# Sheet1.net
KiCad netlist of a schematic drawn in Altium Designer
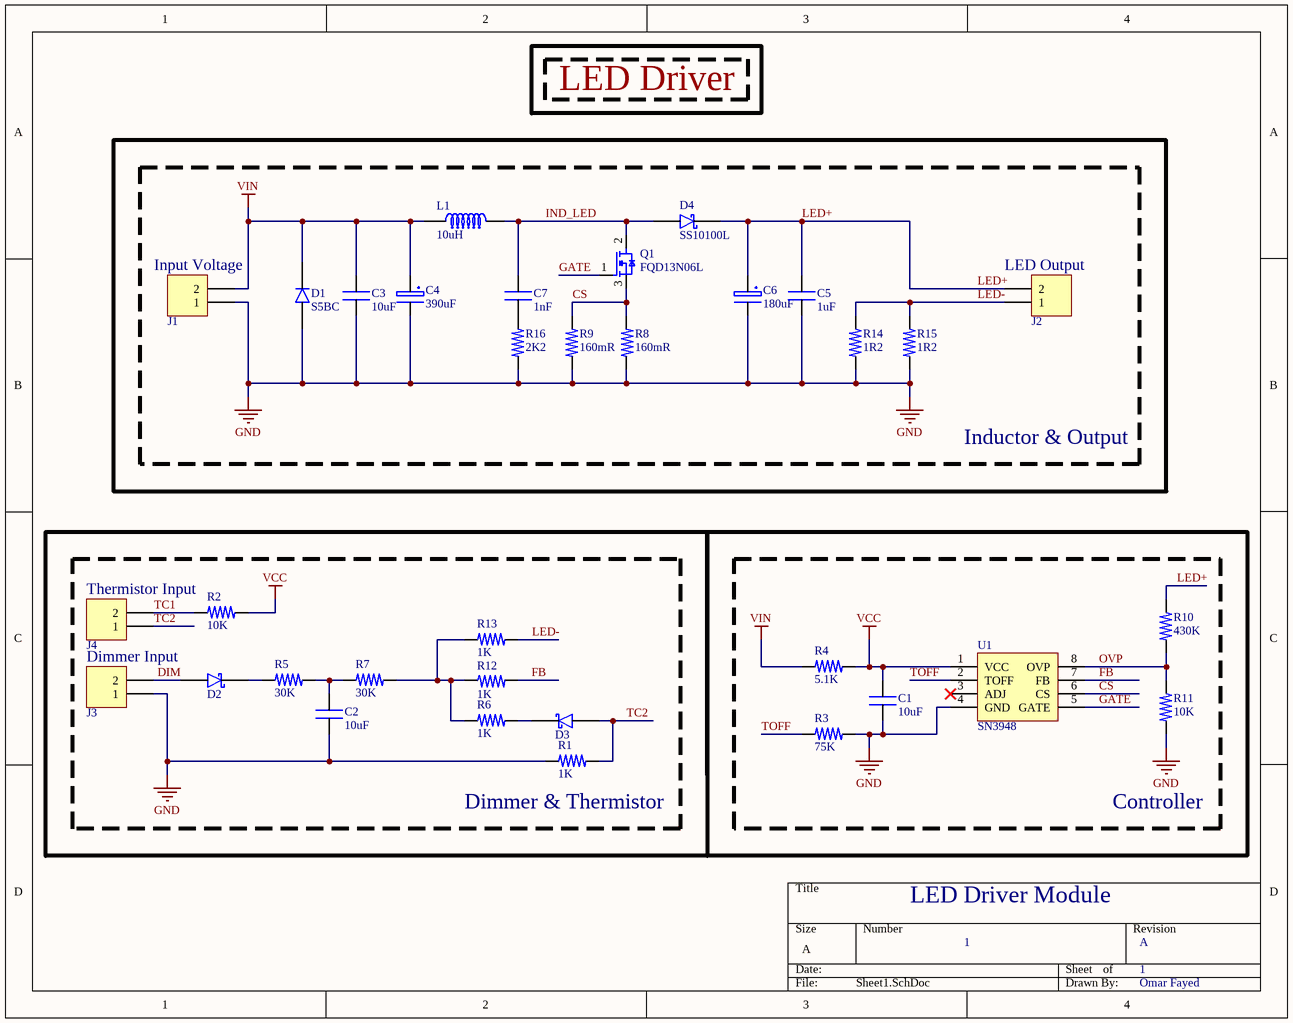
[diagram p0: Sheet1.SchDoc]

(export (version "E")
  (design (tool "Eeschema 10.0.6"))
  (components
    (comp (ref "C1")
      (value "10uF")
      (footprint "CAP Ceramic SMD 0805")
      (description "50V 10uF X5R ±10% 0805 Multilayer Ceramic Capacitors MLCC - SMD/SMT ROHS")
      (fields
        (field (name "MANUFACTURER") "Murata Electronics")
        (field (name "MANUFACTURER PART NUMBER") "GRM21BR61H106KE43L")
      )
      (libsource (lib "Schlib") (part "CAP SMD 0805 10uF 50V"))
    )
    (comp (ref "C2")
      (value "10uF")
      (footprint "CAP Ceramic SMD 0805")
      (description "50V 10uF X5R ±10% 0805 Multilayer Ceramic Capacitors MLCC - SMD/SMT ROHS")
      (fields
        (field (name "MANUFACTURER") "Murata Electronics")
        (field (name "MANUFACTURER PART NUMBER") "GRM21BR61H106KE43L")
      )
      (libsource (lib "Schlib") (part "CAP SMD 0805 10uF 50V"))
    )
    (comp (ref "C3")
      (value "10uF")
      (footprint "CAP Ceramic SMD 0805")
      (description "50V 10uF X5R ±10% 0805 Multilayer Ceramic Capacitors MLCC - SMD/SMT ROHS")
      (fields
        (field (name "MANUFACTURER") "Murata Electronics")
        (field (name "MANUFACTURER PART NUMBER") "GRM21BR61H106KE43L")
      )
      (libsource (lib "Schlib") (part "CAP SMD 0805 10uF 50V"))
    )
    (comp (ref "C4")
      (value "390uF")
      (footprint "CAP Electrolytic TH D8C3.5H11.5 (H)")
      (fields (field (name "MANUFACTURER") "Ymin") (field (name "MANUFACTURER PART NUMBER") "LKME2001J391MF"))
      (libsource (lib "Schlib") (part "CAP POL 390uF 63V"))
    )
    (comp (ref "C5")
      (value "1uF")
      (footprint "CAP Ceramic SMD 1206")
      (description "100V 1uF X7R ±10% 1206 Multilayer Ceramic Capacitors MLCC - SMD/SMT ROHS")
      (fields
        (field (name "MANUFACTURER") "YAGEO")
        (field (name "MANUFACTURER PART NUMBER") "CC1206KKX7R0BB105")
      )
      (libsource (lib "Schlib") (part "CAP SMD 1206 1uF 100V"))
    )
    (comp (ref "C6")
      (value "180uF")
      (footprint "CAP Electrolytic TH D8C3.5H11.5 (H)")
      (fields
        (field (name "MANUFACTURER") "SamYoung Electronics")
        (field (name "MANUFACTURER PART NUMBER") "NXA50V180M8*20 LO")
      )
      (libsource (lib "Schlib") (part "CAP POL 180uF 50V"))
    )
    (comp (ref "C7")
      (value "1nF")
      (footprint "CAP Ceramic SMD 0805")
      (description "100V 1nF NP0 ±5% 0805 Multilayer Ceramic Capacitors MLCC - SMD/SMT ROHS")
      (fields
        (field (name "MANUFACTURER") "YAGEO")
        (field (name "MANUFACTURER PART NUMBER") "CC0805JRNPO0BN102")
      )
      (libsource (lib "Schlib") (part "CAP SMD 0805 1nF"))
    )
    (comp (ref "D1")
      (value "S5BC")
      (footprint "SMC")
      (description "5A 100V 1.15V@5A SMC(DO-214AB) Diodes - General Purpose ROHS")
      (fields
        (field (name "MANUFACTURER") "Diodes Incorporated")
        (field (name "MANUFACTURER PART NUMBER") "S5BC-13-F")
      )
      (libsource (lib "Schlib") (part "S5BC"))
    )
    (comp (ref "D2")
      (value "DIODE SMD BAT54WB")
      (footprint "SOD-323")
      (description "30V 100mA 240mV@100mA SOD-323W Schottky Diodes ROHS")
      (fields
        (field (name "MANUFACTURER") "Shandong Jingdao Microelectronics")
        (field (name "MANUFACTURER PART NUMBER") "BAT54WB")
      )
      (libsource (lib "Schlib") (part "DIODE SMD BAT54WB"))
    )
    (comp (ref "D3")
      (value "DIODE SMD BAT54WB")
      (footprint "SOD-323")
      (description "30V 100mA 240mV@100mA SOD-323W Schottky Diodes ROHS")
      (fields
        (field (name "MANUFACTURER") "Shandong Jingdao Microelectronics")
        (field (name "MANUFACTURER PART NUMBER") "BAT54WB")
      )
      (libsource (lib "Schlib") (part "DIODE SMD BAT54WB"))
    )
    (comp (ref "D4")
      (value "SS10100L")
      (footprint "DO-214AA")
      (description "100V 10A 700mV SMB Schottky Diodes ROHS")
      (fields (field (name "MANUFACTURER") "GOODWORK"))
      (libsource (lib "Schlib") (part "SS10100L"))
    )
    (comp (ref "J1")
      (value "ScrewTerminal 2P mm")
      (footprint "Connector screw terminal Block TH 1x2 9.5 WJ46-B")
      (fields
        (field (name "MANUFACTURER") "MAX")
        (field (name "MANUFACTURER PART NUMBER") "MX126-5.0-02P-GN01-Cu-S-A")
      )
      (libsource (lib "Schlib") (part "ScrewTerminal 2P mm"))
    )
    (comp (ref "J2")
      (value "ScrewTerminal 2P mm")
      (footprint "Connector screw terminal Block TH 1x2 9.5 WJ46-B")
      (fields
        (field (name "MANUFACTURER") "MAX")
        (field (name "MANUFACTURER PART NUMBER") "MX126-5.0-02P-GN01-Cu-S-A")
      )
      (libsource (lib "") (part "ScrewTerminal 2P mm_1"))
    )
    (comp (ref "J3")
      (value "ScrewTerminal 2P mm")
      (footprint "Connector screw terminal Block TH 1x2 9.5 WJ46-B")
      (fields
        (field (name "MANUFACTURER") "MAX")
        (field (name "MANUFACTURER PART NUMBER") "MX126-5.0-02P-GN01-Cu-S-A")
      )
      (libsource (lib "Schlib") (part "ScrewTerminal 2P mm"))
    )
    (comp (ref "J4")
      (value "ScrewTerminal 2P mm")
      (footprint "Connector screw terminal Block TH 1x2 9.5 WJ46-B")
      (fields
        (field (name "MANUFACTURER") "MAX")
        (field (name "MANUFACTURER PART NUMBER") "MX126-5.0-02P-GN01-Cu-S-A")
      )
      (libsource (lib "Schlib") (part "ScrewTerminal 2P mm"))
    )
    (comp (ref "L1")
      (value "10uH")
      (footprint "IND SMD 1365")
      (description "10A 10uH ±20% 13A 19.2mΩ SMD,12.6x13.5mm Inductors (SMD) ROHS")
      (fields
        (field (name "MANUFACTURER") "KOHERelec")
        (field (name "MANUFACTURER PART NUMBER") "MDA1365-100M")
      )
      (libsource (lib "Schlib") (part "IND SMD 1365 10uH"))
    )
    (comp (ref "Q1")
      (value "FQD13N06L")
      (footprint "TO252_2")
      (description "60V 11A 115mΩ@10V,5.5A 2.5V@250uA 1 N-Channel TO-252AA MOSFETs ROHS")
      (fields (field (name "MANUFACTURER") "onsemi") (field (name "MANUFACTURER PART NUMBER") "FQD13N06LTM"))
      (libsource (lib "Schlib") (part "FQD13N06L"))
    )
    (comp (ref "R1")
      (value "1K")
      (footprint "RES SMD 0805")
      (fields
        (field (name "MANUFACTURER") "YAGEO")
        (field (name "MANUFACTURER PART NUMBER") "RC0805FR-071KL")
      )
      (libsource (lib "Schlib") (part "RES SMD 0805 1K"))
    )
    (comp (ref "R2")
      (value "10K")
      (footprint "RES SMD 0805")
      (description "125mW Thick Film Resistors 150V ±100ppm/℃ ±1% 10kΩ 0805 Chip Resistor - Surface Mount ROHS")
      (fields
        (field (name "MANUFACTURER") "YAGEO")
        (field (name "MANUFACTURER PART NUMBER") "RC0805FR-0710KL")
      )
      (libsource (lib "Schlib") (part "RES SMD 0805 10K"))
    )
    (comp (ref "R3")
      (value "75K")
      (footprint "RES SMD 0805")
      (description "125mW Thick Film Resistors 150V ±100ppm/℃ ±1% 75kΩ 0805 Chip Resistor - Surface Mount ROHS")
      (fields
        (field (name "MANUFACTURER") "YAGEO")
        (field (name "MANUFACTURER PART NUMBER") "RC0805FR-0775KL")
      )
      (libsource (lib "Schlib") (part "RES SMD 0805 75K"))
    )
    (comp (ref "R4")
      (value "5.1K")
      (footprint "RES SMD 0805")
      (description "400mW Thick Film Resistors 150V ±200ppm/℃ ±5% 5.1kΩ 0805 Chip Resistor - Surface Mount ROHS")
      (fields
        (field (name "MANUFACTURER") "ROHM Semicon")
        (field (name "MANUFACTURER PART NUMBER") "ESR10EZPJ512")
      )
      (libsource (lib "Schlib") (part "RES SMD 0805 5.1K"))
    )
    (comp (ref "R5")
      (value "30K")
      (footprint "RES SMD 0805")
      (fields (field (name "MANUFACTURER") "FOJAN") (field (name "MANUFACTURER PART NUMBER") "FRC0805J303TS"))
      (libsource (lib "Schlib") (part "RES SMD 0805 30K"))
    )
    (comp (ref "R6")
      (value "1K")
      (footprint "RES SMD 0805")
      (fields
        (field (name "MANUFACTURER") "YAGEO")
        (field (name "MANUFACTURER PART NUMBER") "RC0805FR-071KL")
      )
      (libsource (lib "Schlib") (part "RES SMD 0805 1K"))
    )
    (comp (ref "R7")
      (value "30K")
      (footprint "RES SMD 0805")
      (fields (field (name "MANUFACTURER") "FOJAN") (field (name "MANUFACTURER PART NUMBER") "FRC0805J303TS"))
      (libsource (lib "Schlib") (part "RES SMD 0805 30K"))
    )
    (comp (ref "R8")
      (value "160mR")
      (footprint "RES SMD 1206")
      (description "500mW Thick Film Resistors 200V ±1% 160mΩ 1206 Chip Resistor - Surface Mount ROHS")
      (fields
        (field (name "MANUFACTURER") "UNI-ROYAL(Uniroyal Elec)")
        (field (name "MANUFACTURER PART NUMBER") "HP06W2F160LT5E")
      )
      (libsource (lib "Schlib") (part "RES SMD 1206 160mR"))
    )
    (comp (ref "R9")
      (value "160mR")
      (footprint "RES SMD 1206")
      (description "500mW Thick Film Resistors 200V ±1% 160mΩ 1206 Chip Resistor - Surface Mount ROHS")
      (fields
        (field (name "MANUFACTURER") "UNI-ROYAL(Uniroyal Elec)")
        (field (name "MANUFACTURER PART NUMBER") "HP06W2F160LT5E")
      )
      (libsource (lib "Schlib") (part "RES SMD 1206 160mR"))
    )
    (comp (ref "R10")
      (value "430K")
      (footprint "RES SMD 0805")
      (description "125mW Thick Film Resistors 150V ±100ppm/℃ ±5% 430kΩ 0805 Chip Resistor - Surface Mount ROHS")
      (fields
        (field (name "MANUFACTURER") "YAGEO")
        (field (name "MANUFACTURER PART NUMBER") "RC0805JR-07430KL")
      )
      (libsource (lib "Schlib") (part "RES SMD 0805 430K"))
    )
    (comp (ref "R11")
      (value "10K")
      (footprint "RES SMD 0805")
      (description "125mW Thick Film Resistors 150V ±100ppm/℃ ±1% 10kΩ 0805 Chip Resistor - Surface Mount ROHS")
      (fields
        (field (name "MANUFACTURER") "YAGEO")
        (field (name "MANUFACTURER PART NUMBER") "RC0805FR-0710KL")
      )
      (libsource (lib "Schlib") (part "RES SMD 0805 10K"))
    )
    (comp (ref "R12")
      (value "1K")
      (footprint "RES SMD 0805")
      (fields
        (field (name "MANUFACTURER") "YAGEO")
        (field (name "MANUFACTURER PART NUMBER") "RC0805FR-071KL")
      )
      (libsource (lib "Schlib") (part "RES SMD 0805 1K"))
    )
    (comp (ref "R13")
      (value "1K")
      (footprint "RES SMD 0805")
      (fields
        (field (name "MANUFACTURER") "YAGEO")
        (field (name "MANUFACTURER PART NUMBER") "RC0805FR-071KL")
      )
      (libsource (lib "Schlib") (part "RES SMD 0805 1K"))
    )
    (comp (ref "R14")
      (value "1R2")
      (footprint "RES SMD 1206")
      (description "500mW Thick Film Resistors ±200ppm/℃ ±1% 1.2Ω 1206 Chip Resistor - Surface Mount ROHS")
      (fields
        (field (name "MANUFACTURER") "YAGEO")
        (field (name "MANUFACTURER PART NUMBER") "RC1206FR-7W1R2L")
      )
      (libsource (lib "Schlib") (part "RES SMD 1206 1R20"))
    )
    (comp (ref "R15")
      (value "1R2")
      (footprint "RES SMD 1206")
      (description "500mW Thick Film Resistors ±200ppm/℃ ±1% 1.2Ω 1206 Chip Resistor - Surface Mount ROHS")
      (fields
        (field (name "MANUFACTURER") "YAGEO")
        (field (name "MANUFACTURER PART NUMBER") "RC1206FR-7W1R2L")
      )
      (libsource (lib "Schlib") (part "RES SMD 1206 1R20"))
    )
    (comp (ref "R16")
      (value "2K2")
      (footprint "RES SMD 0805")
      (fields
        (field (name "MANUFACTURER") "YAGEO")
        (field (name "MANUFACTURER PART NUMBER") "RC0805FR-072K2L")
      )
      (libsource (lib "Schlib") (part "RES SMD 0805 2K2"))
    )
    (comp (ref "U1")
      (value "SN3948")
      (footprint "SN3948_SOP8")
      (description "SOP-8 DC-DC Converters ROHS")
      (fields (field (name "MANUFACTURER") "ISSI"))
      (libsource (lib "Schlib") (part "SN3948"))
    )
  )
  (nets
    (net (code "1") (name "/CS") (class "Default")
      (node (ref "Q1") (pin "3") (pinfunction "S_3") (pintype "passive"))
      (node (ref "R8") (pin "1") (pinfunction "1_1") (pintype "passive"))
      (node (ref "R9") (pin "2") (pinfunction "2_2") (pintype "passive"))
      (node (ref "U1") (pin "6") (pinfunction "CS_6") (pintype "passive"))
    )
    (net (code "2") (name "/DIM") (class "Default")
      (node (ref "D2") (pin "1") (pinfunction "1_1") (pintype "passive"))
      (node (ref "J3") (pin "2") (pinfunction "2_2") (pintype "passive"))
    )
    (net (code "3") (name "/FB") (class "Default")
      (node (ref "R12") (pin "1") (pinfunction "1_1") (pintype "passive"))
      (node (ref "U1") (pin "7") (pinfunction "FB_7") (pintype "passive"))
    )
    (net (code "4") (name "/GATE") (class "Default")
      (node (ref "Q1") (pin "1") (pinfunction "G_1") (pintype "passive"))
      (node (ref "U1") (pin "5") (pinfunction "GATE_5") (pintype "passive"))
    )
    (net (code "5") (name "/IND_LED") (class "Default")
      (node (ref "C7") (pin "2") (pinfunction "2_2") (pintype "passive"))
      (node (ref "D4") (pin "1") (pinfunction "1_1") (pintype "passive"))
      (node (ref "L1") (pin "2") (pinfunction "2_2") (pintype "passive"))
      (node (ref "Q1") (pin "2") (pinfunction "D_2") (pintype "passive"))
    )
    (net (code "6") (name "/LED+") (class "Default")
      (node (ref "C5") (pin "2") (pinfunction "2_2") (pintype "passive"))
      (node (ref "C6") (pin "1") (pinfunction "1_1") (pintype "passive"))
      (node (ref "D4") (pin "2") (pinfunction "2_2") (pintype "passive"))
      (node (ref "J2") (pin "2") (pinfunction "2_2") (pintype "passive"))
      (node (ref "R10") (pin "2") (pinfunction "2_2") (pintype "passive"))
    )
    (net (code "7") (name "/LED-") (class "Default")
      (node (ref "J2") (pin "1") (pinfunction "1_1") (pintype "passive"))
      (node (ref "R13") (pin "2") (pinfunction "2_2") (pintype "passive"))
      (node (ref "R14") (pin "2") (pinfunction "2_2") (pintype "passive"))
      (node (ref "R15") (pin "2") (pinfunction "2_2") (pintype "passive"))
    )
    (net (code "8") (name "/OVP") (class "Default")
      (node (ref "R10") (pin "1") (pinfunction "1_1") (pintype "passive"))
      (node (ref "R11") (pin "2") (pinfunction "2_2") (pintype "passive"))
      (node (ref "U1") (pin "8") (pinfunction "OVP_8") (pintype "passive"))
    )
    (net (code "9") (name "/TC1") (class "Default")
      (node (ref "J4") (pin "2") (pinfunction "2_2") (pintype "passive"))
      (node (ref "R2") (pin "1") (pinfunction "1_1") (pintype "passive"))
    )
    (net (code "10") (name "/TC2") (class "Default")
      (node (ref "D3") (pin "1") (pinfunction "1_1") (pintype "passive"))
      (node (ref "J4") (pin "1") (pinfunction "1_1") (pintype "passive"))
      (node (ref "R1") (pin "2") (pinfunction "2_2") (pintype "passive"))
    )
    (net (code "11") (name "/TOFF") (class "Default")
      (node (ref "R3") (pin "1") (pinfunction "1_1") (pintype "passive"))
      (node (ref "U1") (pin "2") (pinfunction "TOFF_2") (pintype "passive"))
    )
    (net (code "12") (name "GND") (class "Default")
      (node (ref "C1") (pin "1") (pinfunction "1_1") (pintype "passive"))
      (node (ref "C2") (pin "1") (pinfunction "1_1") (pintype "passive"))
      (node (ref "C3") (pin "1") (pinfunction "1_1") (pintype "passive"))
      (node (ref "C4") (pin "2") (pinfunction "2_2") (pintype "passive"))
      (node (ref "C5") (pin "1") (pinfunction "1_1") (pintype "passive"))
      (node (ref "C6") (pin "2") (pinfunction "2_2") (pintype "passive"))
      (node (ref "D1") (pin "1") (pinfunction "1_1") (pintype "passive"))
      (node (ref "J1") (pin "1") (pinfunction "1_1") (pintype "passive"))
      (node (ref "J3") (pin "1") (pinfunction "1_1") (pintype "passive"))
      (node (ref "R1") (pin "1") (pinfunction "1_1") (pintype "passive"))
      (node (ref "R11") (pin "1") (pinfunction "1_1") (pintype "passive"))
      (node (ref "R14") (pin "1") (pinfunction "1_1") (pintype "passive"))
      (node (ref "R15") (pin "1") (pinfunction "1_1") (pintype "passive"))
      (node (ref "R16") (pin "1") (pinfunction "1_1") (pintype "passive"))
      (node (ref "R3") (pin "2") (pinfunction "2_2") (pintype "passive"))
      (node (ref "R8") (pin "2") (pinfunction "2_2") (pintype "passive"))
      (node (ref "R9") (pin "1") (pinfunction "1_1") (pintype "passive"))
      (node (ref "U1") (pin "4") (pinfunction "GND_4") (pintype "passive"))
    )
    (net (code "13") (name "Net-(C2-Pad2)") (class "Default")
      (node (ref "C2") (pin "2") (pinfunction "2_2") (pintype "passive"))
      (node (ref "R5") (pin "2") (pinfunction "2_2") (pintype "passive"))
      (node (ref "R7") (pin "1") (pinfunction "1_1") (pintype "passive"))
    )
    (net (code "14") (name "Net-(C7-Pad1)") (class "Default")
      (node (ref "C7") (pin "1") (pinfunction "1_1") (pintype "passive"))
      (node (ref "R16") (pin "2") (pinfunction "2_2") (pintype "passive"))
    )
    (net (code "15") (name "Net-(D2-Pad2)") (class "Default")
      (node (ref "D2") (pin "2") (pinfunction "2_2") (pintype "passive"))
      (node (ref "R5") (pin "1") (pinfunction "1_1") (pintype "passive"))
    )
    (net (code "16") (name "Net-(D3-Pad2)") (class "Default")
      (node (ref "D3") (pin "2") (pinfunction "2_2") (pintype "passive"))
      (node (ref "R6") (pin "2") (pinfunction "2_2") (pintype "passive"))
    )
    (net (code "17") (name "Net-(R12-Pad2)") (class "Default")
      (node (ref "R12") (pin "2") (pinfunction "2_2") (pintype "passive"))
      (node (ref "R13") (pin "1") (pinfunction "1_1") (pintype "passive"))
      (node (ref "R6") (pin "1") (pinfunction "1_1") (pintype "passive"))
      (node (ref "R7") (pin "2") (pinfunction "2_2") (pintype "passive"))
    )
    (net (code "18") (name "VCC") (class "Default")
      (node (ref "C1") (pin "2") (pinfunction "2_2") (pintype "passive"))
      (node (ref "R2") (pin "2") (pinfunction "2_2") (pintype "passive"))
      (node (ref "R4") (pin "2") (pinfunction "2_2") (pintype "passive"))
      (node (ref "U1") (pin "1") (pinfunction "VCC_1") (pintype "passive"))
    )
    (net (code "19") (name "VIN") (class "Default")
      (node (ref "C3") (pin "2") (pinfunction "2_2") (pintype "passive"))
      (node (ref "C4") (pin "1") (pinfunction "1_1") (pintype "passive"))
      (node (ref "D1") (pin "2") (pinfunction "2_2") (pintype "passive"))
      (node (ref "J1") (pin "2") (pinfunction "2_2") (pintype "passive"))
      (node (ref "L1") (pin "1") (pinfunction "1_1") (pintype "passive"))
      (node (ref "R4") (pin "1") (pinfunction "1_1") (pintype "passive"))
    )
    (net (code "20") (name "unconnected-(U1-ADJ-Pad3)") (class "Default")
      (node (ref "U1") (pin "3") (pinfunction "ADJ_3") (pintype "passive+no_connect"))
    )
  )
)
